# JTAG.net
KiCad netlist of a schematic drawn in Altium Designer
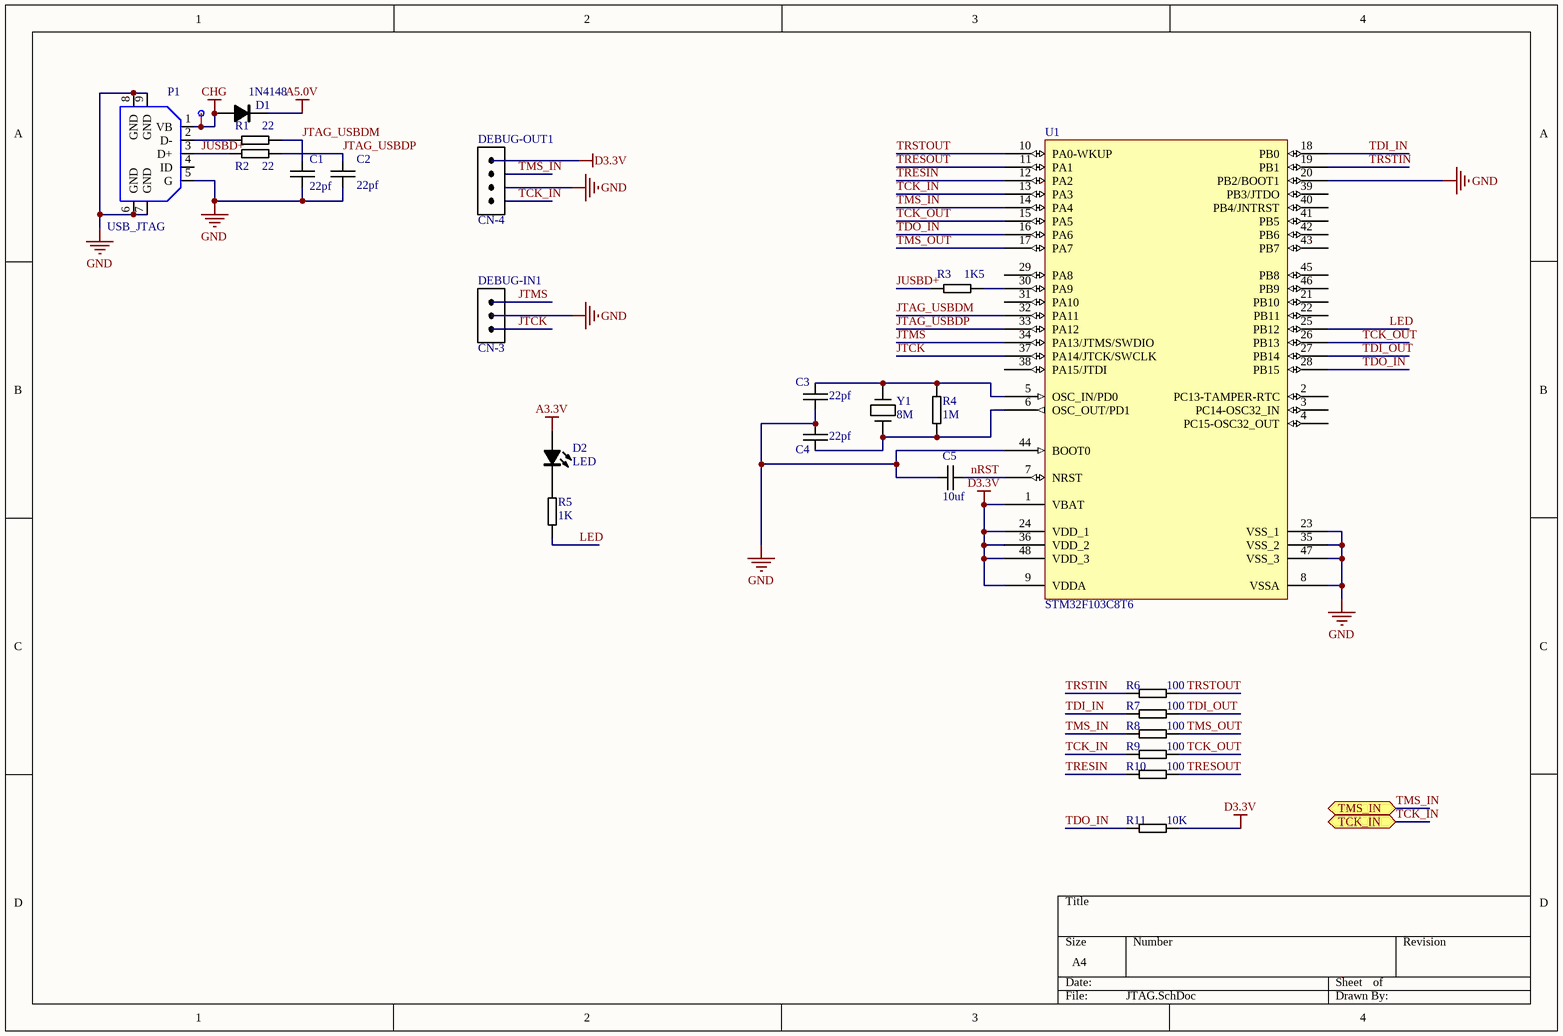
[diagram p0: JTAG.SchDoc]

(export (version "E")
  (design (tool "Eeschema 10.0.6"))
  (components
    (comp (ref "*1") (value "Point") (footprint "Point") (libsource (lib "authuir") (part "Point")))
    (comp (ref "C1")
      (value "22pf")
      (footprint "0805-C")
      (description "贴片")
      (libsource (lib "authuir") (part "CAP_Chip"))
    )
    (comp (ref "C2")
      (value "22pf")
      (footprint "0805-C")
      (description "贴片")
      (libsource (lib "authuir") (part "CAP_Chip"))
    )
    (comp (ref "C3")
      (value "22pf")
      (footprint "0603")
      (description "贴片")
      (libsource (lib "authuir") (part "CAP_Chip"))
    )
    (comp (ref "C4")
      (value "22pf")
      (footprint "0603")
      (description "贴片")
      (libsource (lib "authuir") (part "CAP_Chip"))
    )
    (comp (ref "C5")
      (value "10uf")
      (footprint "0603")
      (description "贴片")
      (libsource (lib "authuir") (part "CAP_Chip"))
    )
    (comp (ref "D1")
      (value "1N4148")
      (footprint "DO-35")
      (description "1.04.08.0001")
      (libsource (lib "晶体管") (part "1N4148(DO-35)"))
    )
    (comp (ref "D2")
      (value "LED")
      (footprint "0805-LED")
      (description "贴片")
      (libsource (lib "authuir") (part "LED"))
    )
    (comp (ref "DEBUG-IN1") (value "CN-3") (footprint "SIP-3") (libsource (lib "开关·连接器") (part "CN-3")))
    (comp (ref "DEBUG-OUT1") (value "CN-4") (footprint "SIP-4") (libsource (lib "开关·连接器") (part "CN-4")))
    (comp (ref "P1")
      (value "USB_JTAG")
      (footprint "USB_Mini_B")
      (libsource (lib "authuir") (part "USB_Mini_B"))
    )
    (comp (ref "R1")
      (value "22")
      (footprint "0805-R")
      (description "贴片")
      (libsource (lib "authuir") (part "RES_Chip"))
    )
    (comp (ref "R2")
      (value "22")
      (footprint "0805-R")
      (description "贴片")
      (libsource (lib "authuir") (part "RES_Chip"))
    )
    (comp (ref "R3")
      (value "1K5")
      (footprint "0603")
      (description "贴片")
      (libsource (lib "authuir") (part "RES_Chip"))
    )
    (comp (ref "R4")
      (value "1M")
      (footprint "0603")
      (description "贴片")
      (libsource (lib "authuir") (part "RES_Chip"))
    )
    (comp (ref "R5")
      (value "1K")
      (footprint "0805-R")
      (description "贴片")
      (libsource (lib "authuir") (part "RES_Chip"))
    )
    (comp (ref "R6")
      (value "100")
      (footprint "0603")
      (description "贴片")
      (libsource (lib "authuir") (part "RES_Chip"))
    )
    (comp (ref "R7")
      (value "100")
      (footprint "0603")
      (description "贴片")
      (libsource (lib "authuir") (part "RES_Chip"))
    )
    (comp (ref "R8")
      (value "100")
      (footprint "0603")
      (description "贴片")
      (libsource (lib "authuir") (part "RES_Chip"))
    )
    (comp (ref "R9")
      (value "100")
      (footprint "0603")
      (description "贴片")
      (libsource (lib "authuir") (part "RES_Chip"))
    )
    (comp (ref "R10")
      (value "100")
      (footprint "0603")
      (description "贴片")
      (libsource (lib "authuir") (part "RES_Chip"))
    )
    (comp (ref "R11")
      (value "10K")
      (footprint "0603")
      (description "贴片")
      (libsource (lib "authuir") (part "RES_Chip"))
    )
    (comp (ref "U1")
      (value "STM32F103C8T6")
      (footprint "LQFP48_N")
      (description "STM32 ARM-based 32-bit MCU with 64 Kbytes Flash, 48-pin LQFP, Industrial Temperature")
      (fields (field (name "PUBLISHER") "Altium Limited"))
      (libsource (lib "ST Microcontroller 32-Bit STM32") (part "STM32F103C8T6"))
    )
    (comp (ref "Y1")
      (value "8M")
      (footprint "XTAL(HC-49)")
      (description "1.07.02.0011")
      (libsource (lib "振荡器") (part "XTAL(12.000M,HC-49US)"))
    )
  )
  (nets
    (net (code "1") (name "/JTAG_USBDM") (class "Default")
      (node (ref "C1") (pin "1") (pinfunction "1_1") (pintype "passive"))
      (node (ref "R1") (pin "2") (pinfunction "2_2") (pintype "passive"))
      (node (ref "U1") (pin "32") (pinfunction "PA11_32") (pintype "bidirectional"))
    )
    (net (code "2") (name "/JTAG_USBDP") (class "Default")
      (node (ref "C2") (pin "1") (pinfunction "1_1") (pintype "passive"))
      (node (ref "R2") (pin "2") (pinfunction "2_2") (pintype "passive"))
      (node (ref "U1") (pin "33") (pinfunction "PA12_33") (pintype "bidirectional"))
    )
    (net (code "3") (name "/JTCK") (class "Default")
      (node (ref "DEBUG-IN1") (pin "3") (pinfunction "3_3") (pintype "passive"))
      (node (ref "U1") (pin "37") (pinfunction "PA14/JTCK/SWCLK_37") (pintype "bidirectional"))
    )
    (net (code "4") (name "/JTMS") (class "Default")
      (node (ref "DEBUG-IN1") (pin "1") (pinfunction "1_1") (pintype "passive"))
      (node (ref "U1") (pin "34") (pinfunction "PA13/JTMS/SWDIO_34") (pintype "bidirectional"))
    )
    (net (code "5") (name "/JUSBD+") (class "Default")
      (node (ref "P1") (pin "3") (pinfunction "D+_3") (pintype "passive"))
      (node (ref "R2") (pin "1") (pinfunction "1_1") (pintype "passive"))
      (node (ref "R3") (pin "1") (pinfunction "1_1") (pintype "passive"))
    )
    (net (code "6") (name "/LED") (class "Default")
      (node (ref "R5") (pin "2") (pinfunction "2_2") (pintype "passive"))
      (node (ref "U1") (pin "25") (pinfunction "PB12_25") (pintype "bidirectional"))
    )
    (net (code "7") (name "/TCK_IN") (class "Default")
      (node (ref "DEBUG-OUT1") (pin "4") (pinfunction "4_4") (pintype "passive"))
      (node (ref "R9") (pin "1") (pinfunction "1_1") (pintype "passive"))
      (node (ref "U1") (pin "13") (pinfunction "PA3_13") (pintype "bidirectional"))
    )
    (net (code "8") (name "/TCK_OUT") (class "Default")
      (node (ref "R9") (pin "2") (pinfunction "2_2") (pintype "passive"))
      (node (ref "U1") (pin "15") (pinfunction "PA5_15") (pintype "bidirectional"))
      (node (ref "U1") (pin "26") (pinfunction "PB13_26") (pintype "bidirectional"))
    )
    (net (code "9") (name "/TDI_IN") (class "Default")
      (node (ref "R7") (pin "1") (pinfunction "1_1") (pintype "passive"))
      (node (ref "U1") (pin "18") (pinfunction "PB0_18") (pintype "bidirectional"))
    )
    (net (code "10") (name "/TDI_OUT") (class "Default")
      (node (ref "R7") (pin "2") (pinfunction "2_2") (pintype "passive"))
      (node (ref "U1") (pin "27") (pinfunction "PB14_27") (pintype "bidirectional"))
    )
    (net (code "11") (name "/TDO_IN") (class "Default")
      (node (ref "R11") (pin "1") (pinfunction "1_1") (pintype "passive"))
      (node (ref "U1") (pin "16") (pinfunction "PA6_16") (pintype "bidirectional"))
      (node (ref "U1") (pin "28") (pinfunction "PB15_28") (pintype "bidirectional"))
    )
    (net (code "12") (name "/TMS_IN") (class "Default")
      (node (ref "DEBUG-OUT1") (pin "2") (pinfunction "2_2") (pintype "passive"))
      (node (ref "R8") (pin "1") (pinfunction "1_1") (pintype "passive"))
      (node (ref "U1") (pin "14") (pinfunction "PA4_14") (pintype "bidirectional"))
    )
    (net (code "13") (name "/TMS_OUT") (class "Default")
      (node (ref "R8") (pin "2") (pinfunction "2_2") (pintype "passive"))
      (node (ref "U1") (pin "17") (pinfunction "PA7_17") (pintype "bidirectional"))
    )
    (net (code "14") (name "/TRESIN") (class "Default")
      (node (ref "R10") (pin "1") (pinfunction "1_1") (pintype "passive"))
      (node (ref "U1") (pin "12") (pinfunction "PA2_12") (pintype "bidirectional"))
    )
    (net (code "15") (name "/TRESOUT") (class "Default")
      (node (ref "R10") (pin "2") (pinfunction "2_2") (pintype "passive"))
      (node (ref "U1") (pin "11") (pinfunction "PA1_11") (pintype "bidirectional"))
    )
    (net (code "16") (name "/TRSTIN") (class "Default")
      (node (ref "R6") (pin "1") (pinfunction "1_1") (pintype "passive"))
      (node (ref "U1") (pin "19") (pinfunction "PB1_19") (pintype "bidirectional"))
    )
    (net (code "17") (name "/TRSTOUT") (class "Default")
      (node (ref "R6") (pin "2") (pinfunction "2_2") (pintype "passive"))
      (node (ref "U1") (pin "10") (pinfunction "PA0-WKUP_10") (pintype "bidirectional"))
    )
    (net (code "18") (name "/nRST") (class "Default")
      (node (ref "C5") (pin "2") (pinfunction "2_2") (pintype "passive"))
      (node (ref "U1") (pin "7") (pinfunction "NRST_7") (pintype "bidirectional"))
    )
    (net (code "19") (name "A3.3V") (class "Default")
      (node (ref "D2") (pin "1") (pinfunction "A_1") (pintype "passive"))
    )
    (net (code "20") (name "A5.0V") (class "Default")
      (node (ref "D1") (pin "2") (pinfunction "K_2") (pintype "passive"))
    )
    (net (code "21") (name "CHG") (class "Default")
      (node (ref "*1") (pin "1") (pinfunction "Point_1") (pintype "passive"))
      (node (ref "D1") (pin "1") (pinfunction "A_1") (pintype "passive"))
      (node (ref "P1") (pin "1") (pinfunction "VB_1") (pintype "passive"))
    )
    (net (code "22") (name "D3.3V") (class "Default")
      (node (ref "DEBUG-OUT1") (pin "1") (pinfunction "1_1") (pintype "passive"))
      (node (ref "R11") (pin "2") (pinfunction "2_2") (pintype "passive"))
      (node (ref "U1") (pin "1") (pinfunction "VBAT_1") (pintype "power_in"))
      (node (ref "U1") (pin "24") (pinfunction "VDD_1_24") (pintype "power_in"))
      (node (ref "U1") (pin "36") (pinfunction "VDD_2_36") (pintype "power_in"))
      (node (ref "U1") (pin "48") (pinfunction "VDD_3_48") (pintype "power_in"))
      (node (ref "U1") (pin "9") (pinfunction "VDDA_9") (pintype "power_in"))
    )
    (net (code "23") (name "GND") (class "Default")
      (node (ref "C1") (pin "2") (pinfunction "2_2") (pintype "passive"))
      (node (ref "C2") (pin "2") (pinfunction "2_2") (pintype "passive"))
      (node (ref "C3") (pin "2") (pinfunction "2_2") (pintype "passive"))
      (node (ref "C4") (pin "1") (pinfunction "1_1") (pintype "passive"))
      (node (ref "C5") (pin "1") (pinfunction "1_1") (pintype "passive"))
      (node (ref "DEBUG-IN1") (pin "2") (pinfunction "2_2") (pintype "passive"))
      (node (ref "DEBUG-OUT1") (pin "3") (pinfunction "3_3") (pintype "passive"))
      (node (ref "P1") (pin "5") (pinfunction "G_5") (pintype "passive"))
      (node (ref "P1") (pin "6") (pinfunction "GND_6") (pintype "passive"))
      (node (ref "P1") (pin "7") (pinfunction "GND_7") (pintype "passive"))
      (node (ref "P1") (pin "8") (pinfunction "GND_8") (pintype "passive"))
      (node (ref "P1") (pin "9") (pinfunction "GND_9") (pintype "passive"))
      (node (ref "U1") (pin "20") (pinfunction "PB2/BOOT1_20") (pintype "bidirectional"))
      (node (ref "U1") (pin "23") (pinfunction "VSS_1_23") (pintype "power_in"))
      (node (ref "U1") (pin "35") (pinfunction "VSS_2_35") (pintype "power_in"))
      (node (ref "U1") (pin "44") (pinfunction "BOOT0_44") (pintype "input"))
      (node (ref "U1") (pin "47") (pinfunction "VSS_3_47") (pintype "power_in"))
      (node (ref "U1") (pin "8") (pinfunction "VSSA_8") (pintype "power_in"))
    )
    (net (code "24") (name "Net-(D2-K)") (class "Default")
      (node (ref "D2") (pin "2") (pinfunction "K_2") (pintype "passive"))
      (node (ref "R5") (pin "1") (pinfunction "1_1") (pintype "passive"))
    )
    (net (code "25") (name "Net-(P1-D-)") (class "Default")
      (node (ref "P1") (pin "2") (pinfunction "D-_2") (pintype "passive"))
      (node (ref "R1") (pin "1") (pinfunction "1_1") (pintype "passive"))
    )
    (net (code "26") (name "Net-(U1-OSC_IN{slash}PD0)") (class "Default")
      (node (ref "C3") (pin "1") (pinfunction "1_1") (pintype "passive"))
      (node (ref "R4") (pin "1") (pinfunction "1_1") (pintype "passive"))
      (node (ref "U1") (pin "5") (pinfunction "OSC_IN/PD0_5") (pintype "input"))
      (node (ref "Y1") (pin "1") (pinfunction "1_1") (pintype "passive"))
    )
    (net (code "27") (name "Net-(U1-OSC_OUT{slash}PD1)") (class "Default")
      (node (ref "C4") (pin "2") (pinfunction "2_2") (pintype "passive"))
      (node (ref "R4") (pin "2") (pinfunction "2_2") (pintype "passive"))
      (node (ref "U1") (pin "6") (pinfunction "OSC_OUT/PD1_6") (pintype "output"))
      (node (ref "Y1") (pin "2") (pinfunction "2_2") (pintype "passive"))
    )
    (net (code "28") (name "Net-(U1-PA9)") (class "Default")
      (node (ref "R3") (pin "2") (pinfunction "2_2") (pintype "passive"))
      (node (ref "U1") (pin "30") (pinfunction "PA9_30") (pintype "bidirectional"))
    )
    (net (code "29") (name "unconnected-(P1-ID-Pad4)") (class "Default")
      (node (ref "P1") (pin "4") (pinfunction "ID_4") (pintype "passive"))
    )
    (net (code "30") (name "unconnected-(U1-PA8-Pad29)") (class "Default")
      (node (ref "U1") (pin "29") (pinfunction "PA8_29") (pintype "bidirectional"))
    )
    (net (code "31") (name "unconnected-(U1-PA10-Pad31)") (class "Default")
      (node (ref "U1") (pin "31") (pinfunction "PA10_31") (pintype "bidirectional"))
    )
    (net (code "32") (name "unconnected-(U1-PA15{slash}JTDI-Pad38)") (class "Default")
      (node (ref "U1") (pin "38") (pinfunction "PA15/JTDI_38") (pintype "bidirectional"))
    )
    (net (code "33") (name "unconnected-(U1-PB3{slash}JTDO-Pad39)") (class "Default")
      (node (ref "U1") (pin "39") (pinfunction "PB3/JTDO_39") (pintype "bidirectional"))
    )
    (net (code "34") (name "unconnected-(U1-PB4{slash}JNTRST-Pad40)") (class "Default")
      (node (ref "U1") (pin "40") (pinfunction "PB4/JNTRST_40") (pintype "bidirectional"))
    )
    (net (code "35") (name "unconnected-(U1-PB5-Pad41)") (class "Default")
      (node (ref "U1") (pin "41") (pinfunction "PB5_41") (pintype "bidirectional"))
    )
    (net (code "36") (name "unconnected-(U1-PB6-Pad42)") (class "Default")
      (node (ref "U1") (pin "42") (pinfunction "PB6_42") (pintype "bidirectional"))
    )
    (net (code "37") (name "unconnected-(U1-PB7-Pad43)") (class "Default")
      (node (ref "U1") (pin "43") (pinfunction "PB7_43") (pintype "bidirectional"))
    )
    (net (code "38") (name "unconnected-(U1-PB8-Pad45)") (class "Default")
      (node (ref "U1") (pin "45") (pinfunction "PB8_45") (pintype "bidirectional"))
    )
    (net (code "39") (name "unconnected-(U1-PB9-Pad46)") (class "Default")
      (node (ref "U1") (pin "46") (pinfunction "PB9_46") (pintype "bidirectional"))
    )
    (net (code "40") (name "unconnected-(U1-PB10-Pad21)") (class "Default")
      (node (ref "U1") (pin "21") (pinfunction "PB10_21") (pintype "bidirectional"))
    )
    (net (code "41") (name "unconnected-(U1-PB11-Pad22)") (class "Default")
      (node (ref "U1") (pin "22") (pinfunction "PB11_22") (pintype "bidirectional"))
    )
    (net (code "42") (name "unconnected-(U1-PC13-TAMPER-RTC-Pad2)") (class "Default")
      (node (ref "U1") (pin "2") (pinfunction "PC13-TAMPER-RTC_2") (pintype "bidirectional"))
    )
    (net (code "43") (name "unconnected-(U1-PC14-OSC32_IN-Pad3)") (class "Default")
      (node (ref "U1") (pin "3") (pinfunction "PC14-OSC32_IN_3") (pintype "bidirectional"))
    )
    (net (code "44") (name "unconnected-(U1-PC15-OSC32_OUT-Pad4)") (class "Default")
      (node (ref "U1") (pin "4") (pinfunction "PC15-OSC32_OUT_4") (pintype "bidirectional"))
    )
  )
)
